# class_a.net
KiCad netlist of a schematic drawn in EAGLE
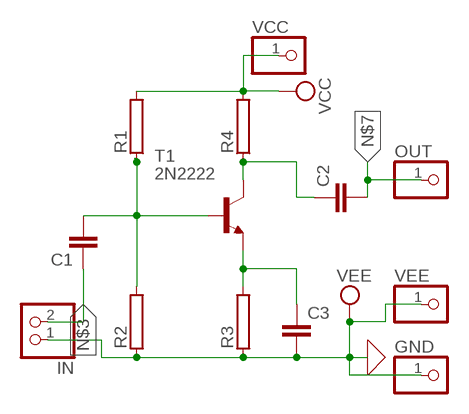
[diagram p0: schematic, sheet 1]

(export (version "E")
  (design (tool "Eeschema 10.0.6"))
  (components
    (comp (ref "C1")
      (value "C2,5-3")
      (footprint "eagle-import:C2.5-3")
      (libsource (lib "eagle-import") (part "C2,5-3"))
    )
    (comp (ref "C2")
      (value "C2,5-3")
      (footprint "eagle-import:C2.5-3")
      (libsource (lib "eagle-import") (part "C2,5-3"))
    )
    (comp (ref "C3")
      (value "C2,5-3")
      (footprint "eagle-import:C2.5-3")
      (libsource (lib "eagle-import") (part "C2,5-3"))
    )
    (comp (ref "GND")
      (value "PINHD-1X1")
      (footprint "eagle-import:1X01")
      (libsource (lib "eagle-import") (part "PINHD-1X1"))
    )
    (comp (ref "IN")
      (value "PINHD-1X2")
      (footprint "eagle-import:1X02")
      (libsource (lib "eagle-import") (part "PINHD-1X2"))
    )
    (comp (ref "OUT")
      (value "PINHD-1X1")
      (footprint "eagle-import:1X01")
      (libsource (lib "eagle-import") (part "PINHD-1X1"))
    )
    (comp (ref "R1")
      (value "RAC01")
      (footprint "eagle-import:AC01")
      (libsource (lib "eagle-import") (part "RAC01"))
    )
    (comp (ref "R2")
      (value "RAC01")
      (footprint "eagle-import:AC01")
      (libsource (lib "eagle-import") (part "RAC01"))
    )
    (comp (ref "R3")
      (value "RAC01")
      (footprint "eagle-import:AC01")
      (libsource (lib "eagle-import") (part "RAC01"))
    )
    (comp (ref "R4")
      (value "RAC01")
      (footprint "eagle-import:AC01")
      (libsource (lib "eagle-import") (part "RAC01"))
    )
    (comp (ref "T1")
      (value "2N2222")
      (footprint "eagle-import:TO18")
      (libsource (lib "eagle-import") (part "2N2222"))
    )
    (comp (ref "VCC")
      (value "PINHD-1X1")
      (footprint "eagle-import:1X01")
      (libsource (lib "eagle-import") (part "PINHD-1X1"))
    )
    (comp (ref "VEE")
      (value "PINHD-1X1")
      (footprint "eagle-import:1X01")
      (libsource (lib "eagle-import") (part "PINHD-1X1"))
    )
  )
  (nets
    (net (code "1") (name "GND") (class "Default")
      (node (ref "C3") (pin "2") (pinfunction "2_2") (pintype "passive"))
      (node (ref "GND") (pin "1") (pinfunction "1_1") (pintype "passive"))
      (node (ref "IN") (pin "1") (pinfunction "1_1") (pintype "passive"))
      (node (ref "R2") (pin "1") (pinfunction "1_1") (pintype "passive"))
      (node (ref "R3") (pin "1") (pinfunction "1_1") (pintype "passive"))
      (node (ref "VEE") (pin "1") (pinfunction "1_1") (pintype "passive"))
    )
    (net (code "2") (name "N$3") (class "Default")
      (node (ref "C1") (pin "1") (pinfunction "1_1") (pintype "passive"))
      (node (ref "IN") (pin "2") (pinfunction "2_2") (pintype "passive"))
    )
    (net (code "3") (name "N$7") (class "Default")
      (node (ref "C2") (pin "2") (pinfunction "2_2") (pintype "passive"))
      (node (ref "OUT") (pin "1") (pinfunction "1_1") (pintype "passive"))
    )
    (net (code "4") (name "Net-(T1-B)") (class "Default")
      (node (ref "C1") (pin "2") (pinfunction "2_2") (pintype "passive"))
      (node (ref "R1") (pin "1") (pinfunction "1_1") (pintype "passive"))
      (node (ref "R2") (pin "2") (pinfunction "2_2") (pintype "passive"))
      (node (ref "T1") (pin "2") (pinfunction "B_2") (pintype "passive"))
    )
    (net (code "5") (name "Net-(T1-C)") (class "Default")
      (node (ref "C2") (pin "1") (pinfunction "1_1") (pintype "passive"))
      (node (ref "R4") (pin "1") (pinfunction "1_1") (pintype "passive"))
      (node (ref "T1") (pin "3") (pinfunction "C_3") (pintype "passive"))
    )
    (net (code "6") (name "Net-(T1-E)") (class "Default")
      (node (ref "C3") (pin "1") (pinfunction "1_1") (pintype "passive"))
      (node (ref "R3") (pin "2") (pinfunction "2_2") (pintype "passive"))
      (node (ref "T1") (pin "1") (pinfunction "E_1") (pintype "passive"))
    )
    (net (code "7") (name "VCC") (class "Default")
      (node (ref "R1") (pin "2") (pinfunction "2_2") (pintype "passive"))
      (node (ref "R4") (pin "2") (pinfunction "2_2") (pintype "passive"))
      (node (ref "VCC") (pin "1") (pinfunction "1_1") (pintype "passive"))
    )
  )
)
